# design.net
KiCad netlist of a schematic drawn in EasyEDA
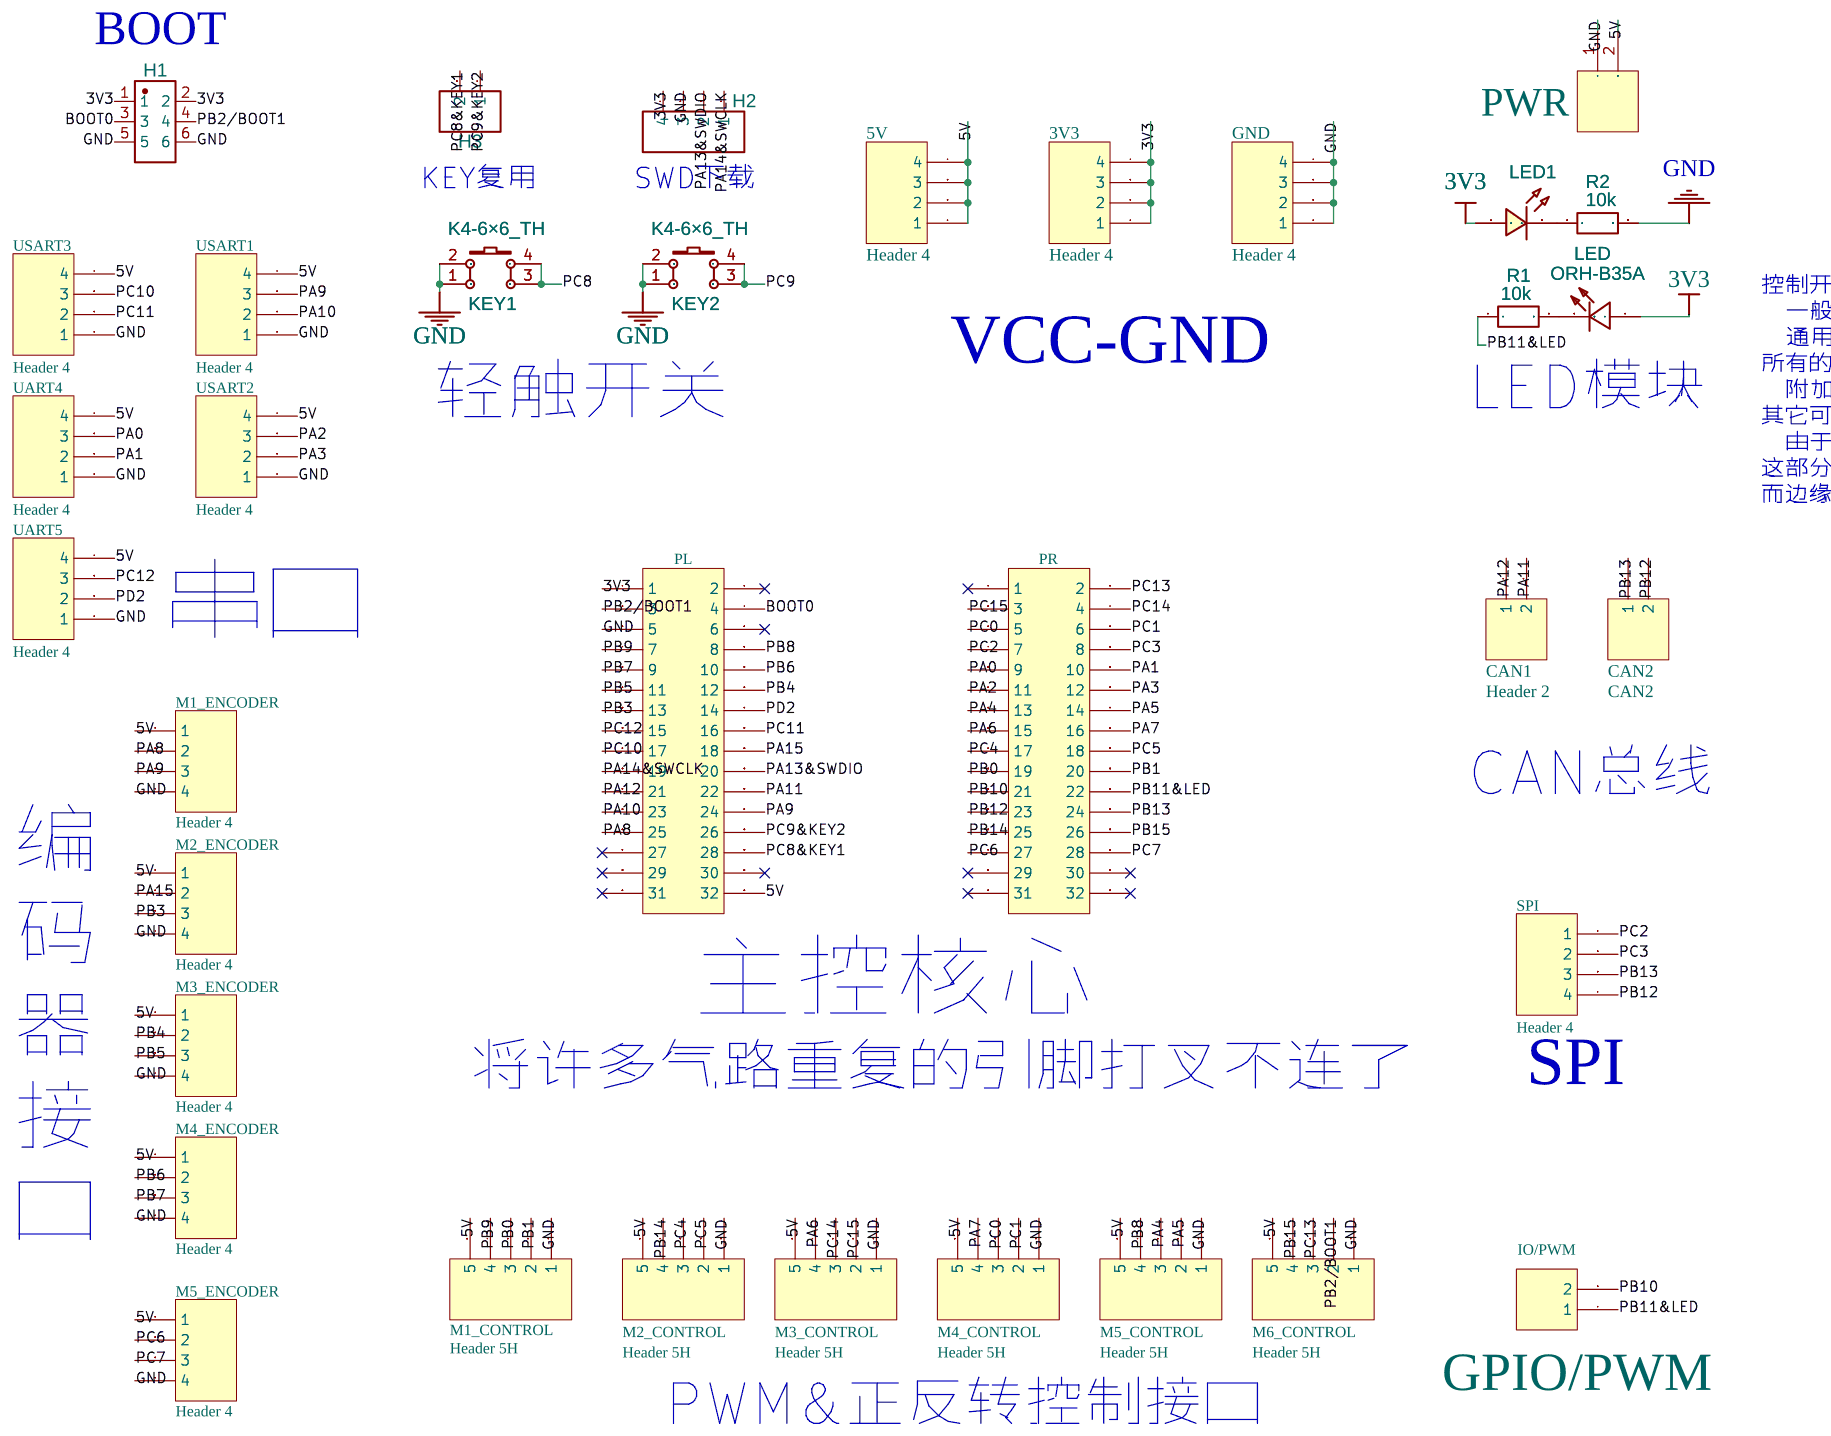
[diagram p0: schematic sheet]

(export (version "E")
  (design (tool "Eeschema 10.0.6"))
  (components
    (comp (ref "3V3") (value "Header 4") (libsource (lib "") (part "Unknown_590_-710")))
    (comp (ref "5V") (value "Header 4") (libsource (lib "") (part "Unknown_500_-710")))
    (comp (ref "CAN1") (value "Header 2") (libsource (lib "") (part "Unknown_805_-535")))
    (comp (ref "CAN2") (value "CAN2") (libsource (lib "") (part "Unknown_865_-535")))
    (comp (ref "GND") (value "Header 4") (libsource (lib "") (part "Unknown_680_-710")))
    (comp (ref "H1")
      (value "PB2为BOOT1设计使用")
      (fields
        (field (name "BOM_Manufacturer Part") "双排针2*3P  脚距2.54mm  贴片")
        (field (name "BOM_Supplier Part") "C77761")
      )
      (libsource (lib "") (part "双排针2*3P  脚距2.54MM  贴片"))
    )
    (comp (ref "H2")
      (value "HDR-F-2.54_1x4")
      (fields (field (name "BOM_Supplier Part") "C225501"))
      (libsource (lib "") (part "HDR-F-2.54_1x4"))
    )
    (comp (ref "H3")
      (value "HDR-F-2.54_1x2")
      (fields (field (name "BOM_Supplier Part") "C49661"))
      (libsource (lib "") (part "HDR-F-2.54_1x2"))
    )
    (comp (ref "IO/PWM") (value "GPIO/PWM") (libsource (lib "") (part "Unknown_820_-175")))
    (comp (ref "KEY1")
      (value "K4-6×6_TH")
      (fields
        (field (name "BOM_Manufacturer Part") "K2-1102DP-E4SW-04")
        (field (name "BOM_Supplier Part") "C136684")
      )
      (libsource (lib "") (part "K4-6×6_TH"))
    )
    (comp (ref "KEY2")
      (value "K4-6×6_TH")
      (fields
        (field (name "BOM_Manufacturer Part") "K2-1102DP-E4SW-04")
        (field (name "BOM_Supplier Part") "C136684")
      )
      (libsource (lib "") (part "K4-6×6_TH"))
    )
    (comp (ref "LED")
      (value "ORH-B35A")
      (fields (field (name "BOM_Supplier Part") "C205441"))
      (libsource (lib "") (part "ORH-B35A"))
    )
    (comp (ref "LED1")
      (value "LED-0805_R")
      (fields
        (field (name "BOM_Manufacturer Part") "17-21SURC/S530-A3/TR8")
        (field (name "BOM_Supplier Part") "C72037")
      )
      (libsource (lib "") (part "LED-0805_R"))
    )
    (comp (ref "M1_CONTROL") (value "Header 5H") (libsource (lib "") (part "Unknown_325_-210")))
    (comp (ref "M1_ENCODER") (value "Header 4") (libsource (lib "") (part "Unknown_130_-480")))
    (comp (ref "M2_CONTROL") (value "Header 5H") (libsource (lib "") (part "Unknown_410_-210")))
    (comp (ref "M2_ENCODER") (value "Header 4") (libsource (lib "") (part "Unknown_130_-410")))
    (comp (ref "M3_CONTROL") (value "Header 5H") (libsource (lib "") (part "Unknown_485_-210")))
    (comp (ref "M3_ENCODER") (value "Header 4") (libsource (lib "") (part "Unknown_130_-340")))
    (comp (ref "M4_CONTROL") (value "Header 5H") (libsource (lib "") (part "Unknown_565_-210")))
    (comp (ref "M4_ENCODER") (value "Header 4") (libsource (lib "") (part "Unknown_130_-270")))
    (comp (ref "M5_CONTROL") (value "Header 5H") (libsource (lib "") (part "Unknown_645_-210")))
    (comp (ref "M5_ENCODER") (value "Header 4") (libsource (lib "") (part "Unknown_130_-190")))
    (comp (ref "M6_CONTROL") (value "Header 5H") (libsource (lib "") (part "Unknown_720_-210")))
    (comp (ref "PL") (value "Header 16X2") (libsource (lib "") (part "Unknown_360_-550")))
    (comp (ref "PR") (value "Header 16X2") (libsource (lib "") (part "Unknown_540_-550")))
    (comp (ref "PWR") (value "HEADER 2") (libsource (lib "") (part "Unknown_850_-795")))
    (comp (ref "R1") (value "10k") (libsource (lib "") (part "R_0805_EU")))
    (comp (ref "R2") (value "10k") (libsource (lib "") (part "R_0805_EU")))
    (comp (ref "SPI") (value "Header 4") (libsource (lib "") (part "Unknown_820_-330")))
    (comp (ref "UART4") (value "Header 4") (libsource (lib "") (part "Unknown_80_-585")))
    (comp (ref "UART5") (value "Header 4") (libsource (lib "") (part "Unknown_80_-515")))
    (comp (ref "USART1") (value "Header 4") (libsource (lib "") (part "Unknown_170_-655")))
    (comp (ref "USART2") (value "Header 4") (libsource (lib "") (part "Unknown_170_-585")))
    (comp (ref "USART3") (value "Header 4") (libsource (lib "") (part "Unknown_80_-655")))
  )
  (nets
    (net (code "1") (name "/5V") (class "Default")
      (node (ref "5V") (pin "1") (pinfunction "1_1") (pintype "unspecified"))
      (node (ref "5V") (pin "2") (pinfunction "2_2") (pintype "unspecified"))
      (node (ref "5V") (pin "3") (pinfunction "3_3") (pintype "unspecified"))
      (node (ref "5V") (pin "4") (pinfunction "4_4") (pintype "unspecified"))
      (node (ref "M1_CONTROL") (pin "5") (pinfunction "5_5") (pintype "unspecified"))
      (node (ref "M1_ENCODER") (pin "1") (pinfunction "1_1") (pintype "unspecified"))
      (node (ref "M2_CONTROL") (pin "5") (pinfunction "5_5") (pintype "unspecified"))
      (node (ref "M2_ENCODER") (pin "1") (pinfunction "1_1") (pintype "unspecified"))
      (node (ref "M3_CONTROL") (pin "5") (pinfunction "5_5") (pintype "unspecified"))
      (node (ref "M3_ENCODER") (pin "1") (pinfunction "1_1") (pintype "unspecified"))
      (node (ref "M4_CONTROL") (pin "5") (pinfunction "5_5") (pintype "unspecified"))
      (node (ref "M4_ENCODER") (pin "1") (pinfunction "1_1") (pintype "unspecified"))
      (node (ref "M5_CONTROL") (pin "5") (pinfunction "5_5") (pintype "unspecified"))
      (node (ref "M5_ENCODER") (pin "1") (pinfunction "1_1") (pintype "unspecified"))
      (node (ref "M6_CONTROL") (pin "5") (pinfunction "5_5") (pintype "unspecified"))
      (node (ref "PL") (pin "32") (pinfunction "32_32") (pintype "unspecified"))
      (node (ref "PWR") (pin "2") (pinfunction "2_2") (pintype "unspecified"))
      (node (ref "UART4") (pin "4") (pinfunction "4_4") (pintype "unspecified"))
      (node (ref "UART5") (pin "4") (pinfunction "4_4") (pintype "unspecified"))
      (node (ref "USART1") (pin "4") (pinfunction "4_4") (pintype "unspecified"))
      (node (ref "USART2") (pin "4") (pinfunction "4_4") (pintype "unspecified"))
      (node (ref "USART3") (pin "4") (pinfunction "4_4") (pintype "unspecified"))
    )
    (net (code "2") (name "/BOOT0") (class "Default")
      (node (ref "H1") (pin "3") (pinfunction "3_3") (pintype "unspecified"))
      (node (ref "PL") (pin "4") (pinfunction "4_4") (pintype "unspecified"))
    )
    (net (code "3") (name "/PA0") (class "Default")
      (node (ref "PR") (pin "9") (pinfunction "9_9") (pintype "unspecified"))
      (node (ref "UART4") (pin "3") (pinfunction "3_3") (pintype "unspecified"))
    )
    (net (code "4") (name "/PA1") (class "Default")
      (node (ref "PR") (pin "10") (pinfunction "10_10") (pintype "unspecified"))
      (node (ref "UART4") (pin "2") (pinfunction "2_2") (pintype "unspecified"))
    )
    (net (code "5") (name "/PA2") (class "Default")
      (node (ref "PR") (pin "11") (pinfunction "11_11") (pintype "unspecified"))
      (node (ref "USART2") (pin "3") (pinfunction "3_3") (pintype "unspecified"))
    )
    (net (code "6") (name "/PA3") (class "Default")
      (node (ref "PR") (pin "12") (pinfunction "12_12") (pintype "unspecified"))
      (node (ref "USART2") (pin "2") (pinfunction "2_2") (pintype "unspecified"))
    )
    (net (code "7") (name "/PA4") (class "Default")
      (node (ref "M5_CONTROL") (pin "3") (pinfunction "3_3") (pintype "unspecified"))
      (node (ref "PR") (pin "13") (pinfunction "13_13") (pintype "unspecified"))
    )
    (net (code "8") (name "/PA5") (class "Default")
      (node (ref "M5_CONTROL") (pin "2") (pinfunction "2_2") (pintype "unspecified"))
      (node (ref "PR") (pin "14") (pinfunction "14_14") (pintype "unspecified"))
    )
    (net (code "9") (name "/PA6") (class "Default")
      (node (ref "M3_CONTROL") (pin "4") (pinfunction "4_4") (pintype "unspecified"))
      (node (ref "PR") (pin "15") (pinfunction "15_15") (pintype "unspecified"))
    )
    (net (code "10") (name "/PA7") (class "Default")
      (node (ref "M4_CONTROL") (pin "4") (pinfunction "4_4") (pintype "unspecified"))
      (node (ref "PR") (pin "16") (pinfunction "16_16") (pintype "unspecified"))
    )
    (net (code "11") (name "/PA8") (class "Default")
      (node (ref "M1_ENCODER") (pin "2") (pinfunction "2_2") (pintype "unspecified"))
      (node (ref "PL") (pin "25") (pinfunction "25_25") (pintype "unspecified"))
    )
    (net (code "12") (name "/PA9") (class "Default")
      (node (ref "M1_ENCODER") (pin "3") (pinfunction "3_3") (pintype "unspecified"))
      (node (ref "PL") (pin "24") (pinfunction "24_24") (pintype "unspecified"))
      (node (ref "USART1") (pin "3") (pinfunction "3_3") (pintype "unspecified"))
    )
    (net (code "13") (name "/PA10") (class "Default")
      (node (ref "PL") (pin "23") (pinfunction "23_23") (pintype "unspecified"))
      (node (ref "USART1") (pin "2") (pinfunction "2_2") (pintype "unspecified"))
    )
    (net (code "14") (name "/PA11") (class "Default")
      (node (ref "CAN1") (pin "2") (pinfunction "2_2") (pintype "unspecified"))
      (node (ref "PL") (pin "22") (pinfunction "22_22") (pintype "unspecified"))
    )
    (net (code "15") (name "/PA12") (class "Default")
      (node (ref "CAN1") (pin "1") (pinfunction "1_1") (pintype "unspecified"))
      (node (ref "PL") (pin "21") (pinfunction "21_21") (pintype "unspecified"))
    )
    (net (code "16") (name "/PA13&SWDIO") (class "Default")
      (node (ref "H2") (pin "2") (pinfunction "2_2") (pintype "unspecified"))
      (node (ref "PL") (pin "20") (pinfunction "20_20") (pintype "unspecified"))
    )
    (net (code "17") (name "/PA14&SWCLK") (class "Default")
      (node (ref "H2") (pin "1") (pinfunction "1_1") (pintype "unspecified"))
      (node (ref "PL") (pin "19") (pinfunction "19_19") (pintype "unspecified"))
    )
    (net (code "18") (name "/PA15") (class "Default")
      (node (ref "M2_ENCODER") (pin "2") (pinfunction "2_2") (pintype "unspecified"))
      (node (ref "PL") (pin "18") (pinfunction "18_18") (pintype "unspecified"))
    )
    (net (code "19") (name "/PB0") (class "Default")
      (node (ref "M1_CONTROL") (pin "3") (pinfunction "3_3") (pintype "unspecified"))
      (node (ref "PR") (pin "19") (pinfunction "19_19") (pintype "unspecified"))
    )
    (net (code "20") (name "/PB1") (class "Default")
      (node (ref "M1_CONTROL") (pin "2") (pinfunction "2_2") (pintype "unspecified"))
      (node (ref "PR") (pin "20") (pinfunction "20_20") (pintype "unspecified"))
    )
    (net (code "21") (name "/PB2{slash}BOOT1") (class "Default")
      (node (ref "H1") (pin "4") (pinfunction "4_4") (pintype "unspecified"))
      (node (ref "M6_CONTROL") (pin "2") (pinfunction "2_2") (pintype "unspecified"))
      (node (ref "PL") (pin "3") (pinfunction "3_3") (pintype "unspecified"))
    )
    (net (code "22") (name "/PB3") (class "Default")
      (node (ref "M2_ENCODER") (pin "3") (pinfunction "3_3") (pintype "unspecified"))
      (node (ref "PL") (pin "13") (pinfunction "13_13") (pintype "unspecified"))
    )
    (net (code "23") (name "/PB4") (class "Default")
      (node (ref "M3_ENCODER") (pin "2") (pinfunction "2_2") (pintype "unspecified"))
      (node (ref "PL") (pin "12") (pinfunction "12_12") (pintype "unspecified"))
    )
    (net (code "24") (name "/PB5") (class "Default")
      (node (ref "M3_ENCODER") (pin "3") (pinfunction "3_3") (pintype "unspecified"))
      (node (ref "PL") (pin "11") (pinfunction "11_11") (pintype "unspecified"))
    )
    (net (code "25") (name "/PB6") (class "Default")
      (node (ref "M4_ENCODER") (pin "2") (pinfunction "2_2") (pintype "unspecified"))
      (node (ref "PL") (pin "10") (pinfunction "10_10") (pintype "unspecified"))
    )
    (net (code "26") (name "/PB7") (class "Default")
      (node (ref "M4_ENCODER") (pin "3") (pinfunction "3_3") (pintype "unspecified"))
      (node (ref "PL") (pin "9") (pinfunction "9_9") (pintype "unspecified"))
    )
    (net (code "27") (name "/PB8") (class "Default")
      (node (ref "M5_CONTROL") (pin "4") (pinfunction "4_4") (pintype "unspecified"))
      (node (ref "PL") (pin "8") (pinfunction "8_8") (pintype "unspecified"))
    )
    (net (code "28") (name "/PB9") (class "Default")
      (node (ref "M1_CONTROL") (pin "4") (pinfunction "4_4") (pintype "unspecified"))
      (node (ref "PL") (pin "7") (pinfunction "7_7") (pintype "unspecified"))
    )
    (net (code "29") (name "/PB10") (class "Default")
      (node (ref "IO/PWM") (pin "2") (pinfunction "2_2") (pintype "unspecified"))
      (node (ref "PR") (pin "21") (pinfunction "21_21") (pintype "unspecified"))
    )
    (net (code "30") (name "/PB11&LED") (class "Default")
      (node (ref "IO/PWM") (pin "1") (pinfunction "1_1") (pintype "unspecified"))
      (node (ref "PR") (pin "22") (pinfunction "22_22") (pintype "unspecified"))
      (node (ref "R1") (pin "1") (pinfunction "1_1") (pintype "unspecified"))
    )
    (net (code "31") (name "/PB12") (class "Default")
      (node (ref "CAN2") (pin "2") (pinfunction "2_2") (pintype "unspecified"))
      (node (ref "PR") (pin "23") (pinfunction "23_23") (pintype "unspecified"))
      (node (ref "SPI") (pin "4") (pinfunction "4_4") (pintype "unspecified"))
    )
    (net (code "32") (name "/PB13") (class "Default")
      (node (ref "CAN2") (pin "1") (pinfunction "1_1") (pintype "unspecified"))
      (node (ref "PR") (pin "24") (pinfunction "24_24") (pintype "unspecified"))
      (node (ref "SPI") (pin "3") (pinfunction "3_3") (pintype "unspecified"))
    )
    (net (code "33") (name "/PB14") (class "Default")
      (node (ref "M2_CONTROL") (pin "4") (pinfunction "4_4") (pintype "unspecified"))
      (node (ref "PR") (pin "25") (pinfunction "25_25") (pintype "unspecified"))
    )
    (net (code "34") (name "/PB15") (class "Default")
      (node (ref "M6_CONTROL") (pin "4") (pinfunction "4_4") (pintype "unspecified"))
      (node (ref "PR") (pin "26") (pinfunction "26_26") (pintype "unspecified"))
    )
    (net (code "35") (name "/PC0") (class "Default")
      (node (ref "M4_CONTROL") (pin "3") (pinfunction "3_3") (pintype "unspecified"))
      (node (ref "PR") (pin "5") (pinfunction "5_5") (pintype "unspecified"))
    )
    (net (code "36") (name "/PC1") (class "Default")
      (node (ref "M4_CONTROL") (pin "2") (pinfunction "2_2") (pintype "unspecified"))
      (node (ref "PR") (pin "6") (pinfunction "6_6") (pintype "unspecified"))
    )
    (net (code "37") (name "/PC2") (class "Default")
      (node (ref "PR") (pin "7") (pinfunction "7_7") (pintype "unspecified"))
      (node (ref "SPI") (pin "1") (pinfunction "1_1") (pintype "unspecified"))
    )
    (net (code "38") (name "/PC3") (class "Default")
      (node (ref "PR") (pin "8") (pinfunction "8_8") (pintype "unspecified"))
      (node (ref "SPI") (pin "2") (pinfunction "2_2") (pintype "unspecified"))
    )
    (net (code "39") (name "/PC4") (class "Default")
      (node (ref "M2_CONTROL") (pin "3") (pinfunction "3_3") (pintype "unspecified"))
      (node (ref "PR") (pin "17") (pinfunction "17_17") (pintype "unspecified"))
    )
    (net (code "40") (name "/PC5") (class "Default")
      (node (ref "M2_CONTROL") (pin "2") (pinfunction "2_2") (pintype "unspecified"))
      (node (ref "PR") (pin "18") (pinfunction "18_18") (pintype "unspecified"))
    )
    (net (code "41") (name "/PC6") (class "Default")
      (node (ref "M5_ENCODER") (pin "2") (pinfunction "2_2") (pintype "unspecified"))
      (node (ref "PR") (pin "27") (pinfunction "27_27") (pintype "unspecified"))
    )
    (net (code "42") (name "/PC7") (class "Default")
      (node (ref "M5_ENCODER") (pin "3") (pinfunction "3_3") (pintype "unspecified"))
      (node (ref "PR") (pin "28") (pinfunction "28_28") (pintype "unspecified"))
    )
    (net (code "43") (name "/PC8") (class "Default")
      (node (ref "KEY1") (pin "3") (pinfunction "3_3") (pintype "unspecified"))
      (node (ref "KEY1") (pin "4") (pinfunction "4_4") (pintype "unspecified"))
    )
    (net (code "44") (name "/PC8&KEY1") (class "Default")
      (node (ref "H3") (pin "2") (pinfunction "2_2") (pintype "input"))
      (node (ref "PL") (pin "28") (pinfunction "28_28") (pintype "unspecified"))
    )
    (net (code "45") (name "/PC9") (class "Default")
      (node (ref "KEY2") (pin "3") (pinfunction "3_3") (pintype "unspecified"))
      (node (ref "KEY2") (pin "4") (pinfunction "4_4") (pintype "unspecified"))
    )
    (net (code "46") (name "/PC9&KEY2") (class "Default")
      (node (ref "H3") (pin "1") (pinfunction "1_1") (pintype "input"))
      (node (ref "PL") (pin "26") (pinfunction "26_26") (pintype "unspecified"))
    )
    (net (code "47") (name "/PC10") (class "Default")
      (node (ref "PL") (pin "17") (pinfunction "17_17") (pintype "unspecified"))
      (node (ref "USART3") (pin "3") (pinfunction "3_3") (pintype "unspecified"))
    )
    (net (code "48") (name "/PC11") (class "Default")
      (node (ref "PL") (pin "16") (pinfunction "16_16") (pintype "unspecified"))
      (node (ref "USART3") (pin "2") (pinfunction "2_2") (pintype "unspecified"))
    )
    (net (code "49") (name "/PC12") (class "Default")
      (node (ref "PL") (pin "15") (pinfunction "15_15") (pintype "unspecified"))
      (node (ref "UART5") (pin "3") (pinfunction "3_3") (pintype "unspecified"))
    )
    (net (code "50") (name "/PC13") (class "Default")
      (node (ref "M6_CONTROL") (pin "3") (pinfunction "3_3") (pintype "unspecified"))
      (node (ref "PR") (pin "2") (pinfunction "2_2") (pintype "unspecified"))
    )
    (net (code "51") (name "/PC14") (class "Default")
      (node (ref "M3_CONTROL") (pin "3") (pinfunction "3_3") (pintype "unspecified"))
      (node (ref "PR") (pin "4") (pinfunction "4_4") (pintype "unspecified"))
    )
    (net (code "52") (name "/PC15") (class "Default")
      (node (ref "M3_CONTROL") (pin "2") (pinfunction "2_2") (pintype "unspecified"))
      (node (ref "PR") (pin "3") (pinfunction "3_3") (pintype "unspecified"))
    )
    (net (code "53") (name "/PD2") (class "Default")
      (node (ref "PL") (pin "14") (pinfunction "14_14") (pintype "unspecified"))
      (node (ref "UART5") (pin "2") (pinfunction "2_2") (pintype "unspecified"))
    )
    (net (code "54") (name "3V3") (class "Default")
      (node (ref "3V3") (pin "1") (pinfunction "1_1") (pintype "unspecified"))
      (node (ref "3V3") (pin "2") (pinfunction "2_2") (pintype "unspecified"))
      (node (ref "3V3") (pin "3") (pinfunction "3_3") (pintype "unspecified"))
      (node (ref "3V3") (pin "4") (pinfunction "4_4") (pintype "unspecified"))
      (node (ref "H1") (pin "1") (pinfunction "1_1") (pintype "unspecified"))
      (node (ref "H1") (pin "2") (pinfunction "2_2") (pintype "unspecified"))
      (node (ref "H2") (pin "4") (pinfunction "4_4") (pintype "unspecified"))
      (node (ref "LED") (pin "1") (pinfunction "A_1") (pintype "unspecified"))
      (node (ref "LED1") (pin "1") (pinfunction "1_1") (pintype "unspecified"))
      (node (ref "PL") (pin "1") (pinfunction "1_1") (pintype "unspecified"))
    )
    (net (code "55") (name "GND") (class "Default")
      (node (ref "GND") (pin "1") (pinfunction "1_1") (pintype "unspecified"))
      (node (ref "GND") (pin "2") (pinfunction "2_2") (pintype "unspecified"))
      (node (ref "GND") (pin "3") (pinfunction "3_3") (pintype "unspecified"))
      (node (ref "GND") (pin "4") (pinfunction "4_4") (pintype "unspecified"))
      (node (ref "H1") (pin "5") (pinfunction "5_5") (pintype "unspecified"))
      (node (ref "H1") (pin "6") (pinfunction "6_6") (pintype "unspecified"))
      (node (ref "H2") (pin "3") (pinfunction "3_3") (pintype "unspecified"))
      (node (ref "KEY1") (pin "1") (pinfunction "1_1") (pintype "unspecified"))
      (node (ref "KEY1") (pin "2") (pinfunction "2_2") (pintype "unspecified"))
      (node (ref "KEY2") (pin "1") (pinfunction "1_1") (pintype "unspecified"))
      (node (ref "KEY2") (pin "2") (pinfunction "2_2") (pintype "unspecified"))
      (node (ref "M1_CONTROL") (pin "1") (pinfunction "1_1") (pintype "unspecified"))
      (node (ref "M1_ENCODER") (pin "4") (pinfunction "4_4") (pintype "unspecified"))
      (node (ref "M2_CONTROL") (pin "1") (pinfunction "1_1") (pintype "unspecified"))
      (node (ref "M2_ENCODER") (pin "4") (pinfunction "4_4") (pintype "unspecified"))
      (node (ref "M3_CONTROL") (pin "1") (pinfunction "1_1") (pintype "unspecified"))
      (node (ref "M3_ENCODER") (pin "4") (pinfunction "4_4") (pintype "unspecified"))
      (node (ref "M4_CONTROL") (pin "1") (pinfunction "1_1") (pintype "unspecified"))
      (node (ref "M4_ENCODER") (pin "4") (pinfunction "4_4") (pintype "unspecified"))
      (node (ref "M5_CONTROL") (pin "1") (pinfunction "1_1") (pintype "unspecified"))
      (node (ref "M5_ENCODER") (pin "4") (pinfunction "4_4") (pintype "unspecified"))
      (node (ref "M6_CONTROL") (pin "1") (pinfunction "1_1") (pintype "unspecified"))
      (node (ref "PL") (pin "5") (pinfunction "5_5") (pintype "unspecified"))
      (node (ref "PWR") (pin "1") (pinfunction "1_1") (pintype "unspecified"))
      (node (ref "R2") (pin "2") (pinfunction "2_2") (pintype "unspecified"))
      (node (ref "UART4") (pin "1") (pinfunction "1_1") (pintype "unspecified"))
      (node (ref "UART5") (pin "1") (pinfunction "1_1") (pintype "unspecified"))
      (node (ref "USART1") (pin "1") (pinfunction "1_1") (pintype "unspecified"))
      (node (ref "USART2") (pin "1") (pinfunction "1_1") (pintype "unspecified"))
      (node (ref "USART3") (pin "1") (pinfunction "1_1") (pintype "unspecified"))
    )
    (net (code "56") (name "Net-(LED-C)") (class "Default")
      (node (ref "LED") (pin "2") (pinfunction "C_2") (pintype "unspecified"))
      (node (ref "R1") (pin "2") (pinfunction "2_2") (pintype "unspecified"))
    )
    (net (code "57") (name "Net-(LED1-Pad2)") (class "Default")
      (node (ref "LED1") (pin "2") (pinfunction "2_2") (pintype "unspecified"))
      (node (ref "R2") (pin "1") (pinfunction "1_1") (pintype "unspecified"))
    )
    (net (code "58") (name "unconnected-(PL-Pad2)") (class "Default")
      (node (ref "PL") (pin "2") (pinfunction "2_2") (pintype "unspecified+no_connect"))
    )
    (net (code "59") (name "unconnected-(PL-Pad6)") (class "Default")
      (node (ref "PL") (pin "6") (pinfunction "6_6") (pintype "unspecified+no_connect"))
    )
    (net (code "60") (name "unconnected-(PL-Pad27)") (class "Default")
      (node (ref "PL") (pin "27") (pinfunction "27_27") (pintype "unspecified+no_connect"))
    )
    (net (code "61") (name "unconnected-(PL-Pad29)") (class "Default")
      (node (ref "PL") (pin "29") (pinfunction "29_29") (pintype "unspecified+no_connect"))
    )
    (net (code "62") (name "unconnected-(PL-Pad30)") (class "Default")
      (node (ref "PL") (pin "30") (pinfunction "30_30") (pintype "unspecified+no_connect"))
    )
    (net (code "63") (name "unconnected-(PL-Pad31)") (class "Default")
      (node (ref "PL") (pin "31") (pinfunction "31_31") (pintype "unspecified+no_connect"))
    )
    (net (code "64") (name "unconnected-(PR-Pad1)") (class "Default")
      (node (ref "PR") (pin "1") (pinfunction "1_1") (pintype "unspecified+no_connect"))
    )
    (net (code "65") (name "unconnected-(PR-Pad29)") (class "Default")
      (node (ref "PR") (pin "29") (pinfunction "29_29") (pintype "unspecified+no_connect"))
    )
    (net (code "66") (name "unconnected-(PR-Pad30)") (class "Default")
      (node (ref "PR") (pin "30") (pinfunction "30_30") (pintype "unspecified+no_connect"))
    )
    (net (code "67") (name "unconnected-(PR-Pad31)") (class "Default")
      (node (ref "PR") (pin "31") (pinfunction "31_31") (pintype "unspecified+no_connect"))
    )
    (net (code "68") (name "unconnected-(PR-Pad32)") (class "Default")
      (node (ref "PR") (pin "32") (pinfunction "32_32") (pintype "unspecified+no_connect"))
    )
  )
)
